# Smartbox.net
KiCad netlist of a schematic drawn in EAGLE
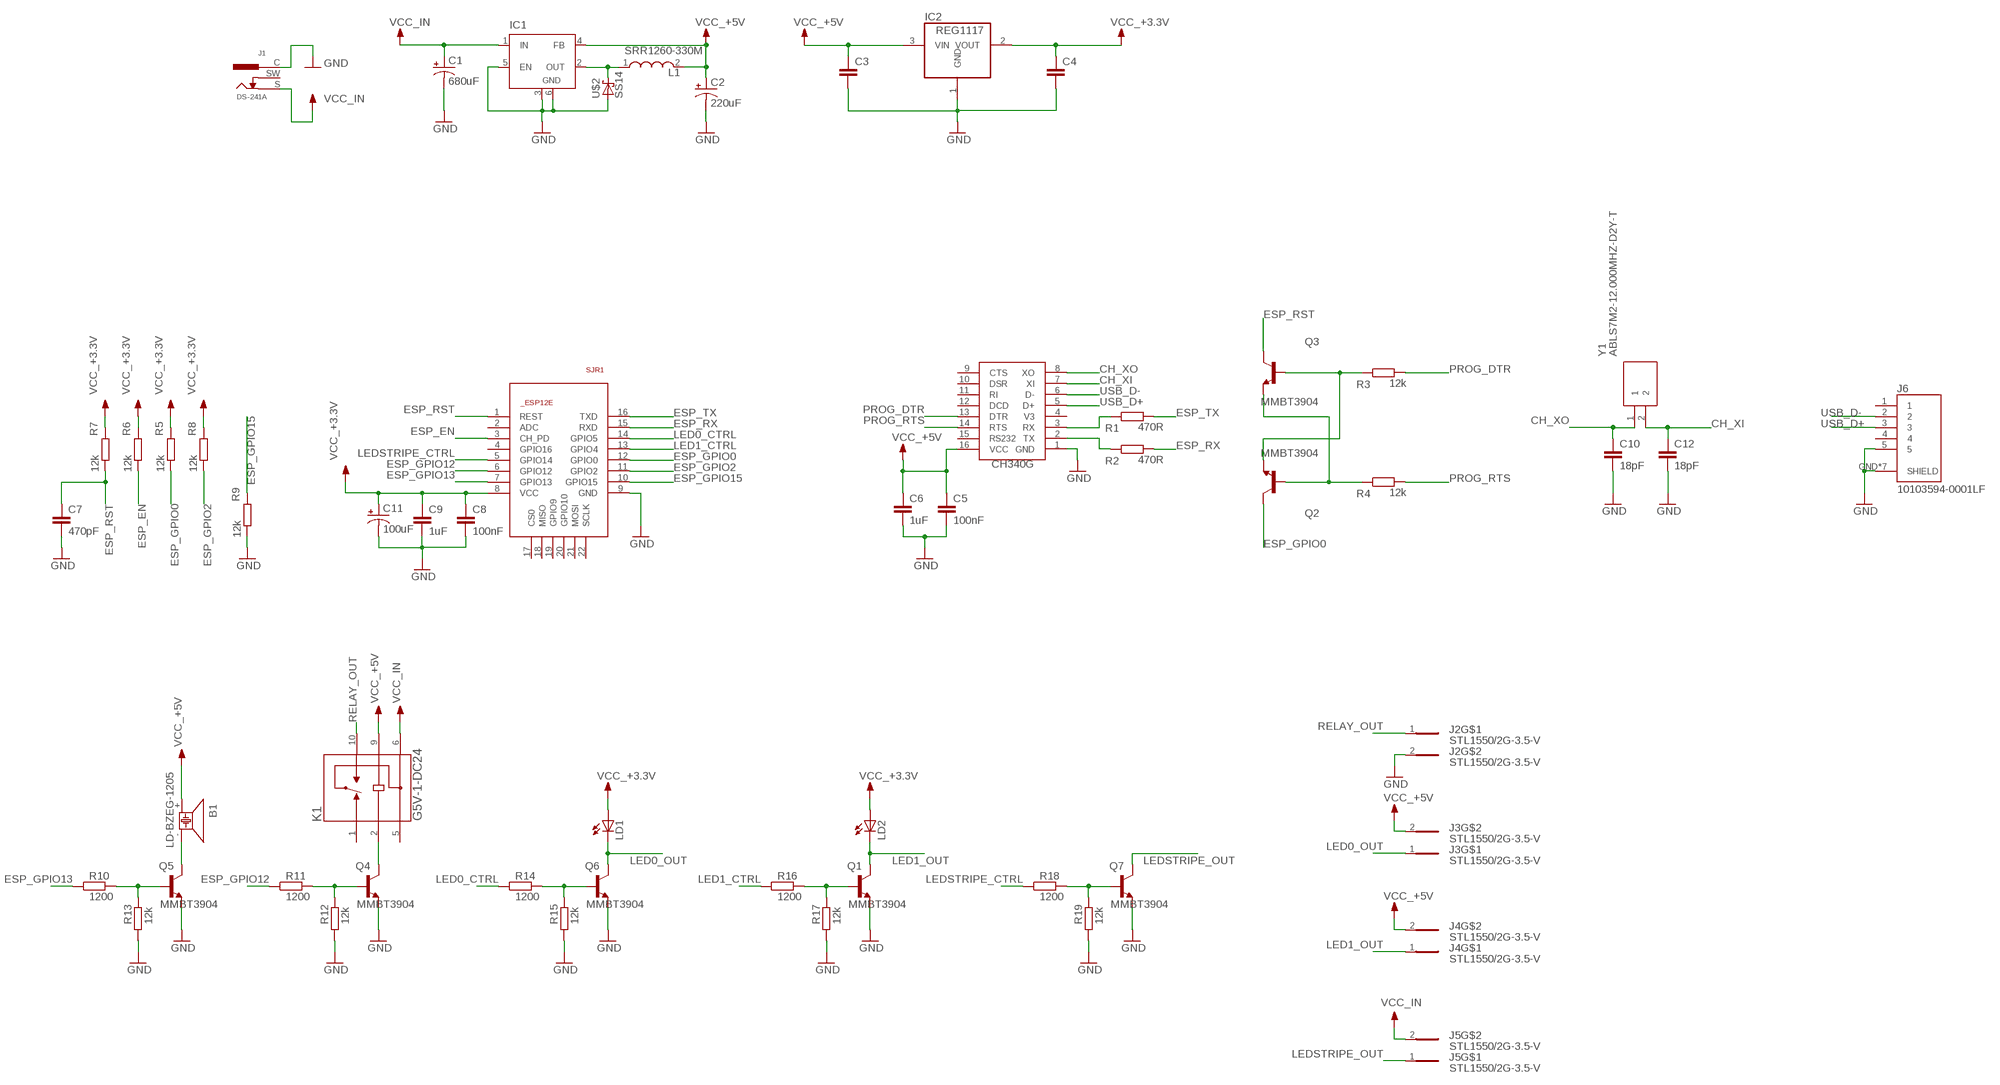
[diagram p0: schematic, sheet 1]

(export (version "E")
  (design (tool "Eeschema 10.0.6"))
  (components
    (comp (ref "B1")
      (value "LD-BZEG-1205")
      (footprint "eagle-import:LD-BZEG-12XX")
      (libsource (lib "eagle-import") (part "LD-BZEG-1205"))
    )
    (comp (ref "C1")
      (value "680uF")
      (footprint "eagle-import:PANASONIC_D")
      (libsource (lib "eagle-import") (part "100UF-POLAR-25V-20%(ELEC)"))
    )
    (comp (ref "C2")
      (value "220uF")
      (footprint "eagle-import:PANASONIC_D")
      (libsource (lib "eagle-import") (part "100UF-POLAR-25V-20%(ELEC)"))
    )
    (comp (ref "C3")
      (value "C-EUC0805")
      (footprint "eagle-import:C0805")
      (libsource (lib "eagle-import") (part "C-EUC0805"))
    )
    (comp (ref "C4")
      (value "C-EUC0805")
      (footprint "eagle-import:C0805")
      (libsource (lib "eagle-import") (part "C-EUC0805"))
    )
    (comp (ref "C5")
      (value "100nF")
      (footprint "eagle-import:C0805")
      (libsource (lib "eagle-import") (part "C-EUC0805"))
    )
    (comp (ref "C6")
      (value "1uF")
      (footprint "eagle-import:C0805")
      (libsource (lib "eagle-import") (part "C-EUC0805"))
    )
    (comp (ref "C7")
      (value "470pF")
      (footprint "eagle-import:C0805")
      (libsource (lib "eagle-import") (part "C-EUC0805"))
    )
    (comp (ref "C8")
      (value "100nF")
      (footprint "eagle-import:C0805")
      (libsource (lib "eagle-import") (part "C-EUC0805"))
    )
    (comp (ref "C9")
      (value "1uF")
      (footprint "eagle-import:C0805")
      (libsource (lib "eagle-import") (part "C-EUC0805"))
    )
    (comp (ref "C10")
      (value "18pF")
      (footprint "eagle-import:C0805")
      (libsource (lib "eagle-import") (part "C-EUC0805"))
    )
    (comp (ref "C11")
      (value "100uF")
      (footprint "eagle-import:PANASONIC_D")
      (libsource (lib "eagle-import") (part "100UF-POLAR-25V-20%(ELEC)"))
    )
    (comp (ref "C12")
      (value "18pF")
      (footprint "eagle-import:C0805")
      (libsource (lib "eagle-import") (part "C-EUC0805"))
    )
    (comp (ref "IC1")
      (value "LM2596S")
      (footprint "eagle-import:TO263-5")
      (libsource (lib "eagle-import") (part "LM2596S"))
    )
    (comp (ref "IC2")
      (value "REG1117")
      (footprint "eagle-import:SOT223")
      (libsource (lib "eagle-import") (part "REG1117"))
    )
    (comp (ref "J1")
      (value "DS-241A")
      (footprint "eagle-import:DS-241")
      (libsource (lib "eagle-import") (part "DS-241A"))
    )
    (comp (ref "J2")
      (value "STL1550/2G-3.5-V")
      (footprint "eagle-import:STL1550_2G-3.5-V-GREEN")
      (libsource (lib "eagle-import") (part "STL1550/2G-3.5-V"))
    )
    (comp (ref "J3")
      (value "STL1550/2G-3.5-V")
      (footprint "eagle-import:STL1550_2G-3.5-V-GREEN")
      (libsource (lib "eagle-import") (part "STL1550/2G-3.5-V"))
    )
    (comp (ref "J4")
      (value "STL1550/2G-3.5-V")
      (footprint "eagle-import:STL1550_2G-3.5-V-GREEN")
      (libsource (lib "eagle-import") (part "STL1550/2G-3.5-V"))
    )
    (comp (ref "J5")
      (value "STL1550/2G-3.5-V")
      (footprint "eagle-import:STL1550_2G-3.5-V-GREEN")
      (libsource (lib "eagle-import") (part "STL1550/2G-3.5-V"))
    )
    (comp (ref "J6")
      (value "10103594-0001LF")
      (footprint "eagle-import:10103594-0001LF")
      (fields
        (field (name "DIGIKEY_PART_NUMBER") "609-4050-2-ND")
        (field (name "MANUFACTURER") "Amphenol ICC (FCI)")
        (field (name "CREATED_BY") "PCBLayout.com")
      )
      (libsource (lib "eagle-import") (part "10103594-0001LF"))
    )
    (comp (ref "K1")
      (value "G5V-1-DC24")
      (footprint "eagle-import:G5V-1-DC24")
      (fields
        (field (name "MANUFACTURER") "Omron Electronics Inc-EMC Div")
        (field (name "CREATED_BY") "  PCBLayout.com")
      )
      (libsource (lib "eagle-import") (part "G5V-1-DC24"))
    )
    (comp (ref "L1")
      (value "SRR1260-330M")
      (footprint "eagle-import:SRR1260-150M")
      (fields (field (name "MOUSER_PART_NUMBER") "652-SRR1260-330M"))
      (libsource (lib "eagle-import") (part "SRR1260-330M"))
    )
    (comp (ref "LD1")
      (value "LEDCHIPLED_0805")
      (footprint "eagle-import:CHIPLED_0805")
      (libsource (lib "eagle-import") (part "LEDCHIPLED_0805"))
    )
    (comp (ref "LD2")
      (value "LEDCHIPLED_0805")
      (footprint "eagle-import:CHIPLED_0805")
      (libsource (lib "eagle-import") (part "LEDCHIPLED_0805"))
    )
    (comp (ref "Q1")
      (value "MMBT3904")
      (footprint "eagle-import:SOT23")
      (fields
        (field (name "DIGIKEY_PART_NUMBER") "MMBT3904FSCT-ND")
        (field (name "MANUFACTURER") "ON Semiconductor")
        (field (name "CREATED_BY") "PCBLayout.com")
      )
      (libsource (lib "eagle-import") (part "MMBT3904"))
    )
    (comp (ref "Q2")
      (value "MMBT3904")
      (footprint "eagle-import:SOT23")
      (fields
        (field (name "DIGIKEY_PART_NUMBER") "MMBT3904FSCT-ND")
        (field (name "MANUFACTURER") "ON Semiconductor")
        (field (name "CREATED_BY") "PCBLayout.com")
      )
      (libsource (lib "eagle-import") (part "MMBT3904"))
    )
    (comp (ref "Q3")
      (value "MMBT3904")
      (footprint "eagle-import:SOT23")
      (fields
        (field (name "DIGIKEY_PART_NUMBER") "MMBT3904FSCT-ND")
        (field (name "MANUFACTURER") "ON Semiconductor")
        (field (name "CREATED_BY") "PCBLayout.com")
      )
      (libsource (lib "eagle-import") (part "MMBT3904"))
    )
    (comp (ref "Q4")
      (value "MMBT3904")
      (footprint "eagle-import:SOT23")
      (fields
        (field (name "DIGIKEY_PART_NUMBER") "MMBT3904FSCT-ND")
        (field (name "MANUFACTURER") "ON Semiconductor")
        (field (name "CREATED_BY") "PCBLayout.com")
      )
      (libsource (lib "eagle-import") (part "MMBT3904"))
    )
    (comp (ref "Q5")
      (value "MMBT3904")
      (footprint "eagle-import:SOT23")
      (fields
        (field (name "DIGIKEY_PART_NUMBER") "MMBT3904FSCT-ND")
        (field (name "MANUFACTURER") "ON Semiconductor")
        (field (name "CREATED_BY") "PCBLayout.com")
      )
      (libsource (lib "eagle-import") (part "MMBT3904"))
    )
    (comp (ref "Q6")
      (value "MMBT3904")
      (footprint "eagle-import:SOT23")
      (fields
        (field (name "DIGIKEY_PART_NUMBER") "MMBT3904FSCT-ND")
        (field (name "MANUFACTURER") "ON Semiconductor")
        (field (name "CREATED_BY") "PCBLayout.com")
      )
      (libsource (lib "eagle-import") (part "MMBT3904"))
    )
    (comp (ref "Q7")
      (value "MMBT3904")
      (footprint "eagle-import:SOT23")
      (fields
        (field (name "DIGIKEY_PART_NUMBER") "MMBT3904FSCT-ND")
        (field (name "MANUFACTURER") "ON Semiconductor")
        (field (name "CREATED_BY") "PCBLayout.com")
      )
      (libsource (lib "eagle-import") (part "MMBT3904"))
    )
    (comp (ref "R1")
      (value "470R")
      (footprint "eagle-import:R0805")
      (libsource (lib "eagle-import") (part "R-EU_R0805"))
    )
    (comp (ref "R2")
      (value "470R")
      (footprint "eagle-import:R0805")
      (libsource (lib "eagle-import") (part "R-EU_R0805"))
    )
    (comp (ref "R3")
      (value "12k")
      (footprint "eagle-import:R0805")
      (libsource (lib "eagle-import") (part "R-EU_R0805"))
    )
    (comp (ref "R4")
      (value "12k")
      (footprint "eagle-import:R0805")
      (libsource (lib "eagle-import") (part "R-EU_R0805"))
    )
    (comp (ref "R5")
      (value "12k")
      (footprint "eagle-import:R0805")
      (libsource (lib "eagle-import") (part "R-EU_R0805"))
    )
    (comp (ref "R6")
      (value "12k")
      (footprint "eagle-import:R0805")
      (libsource (lib "eagle-import") (part "R-EU_R0805"))
    )
    (comp (ref "R7")
      (value "12k")
      (footprint "eagle-import:R0805")
      (libsource (lib "eagle-import") (part "R-EU_R0805"))
    )
    (comp (ref "R8")
      (value "12k")
      (footprint "eagle-import:R0805")
      (libsource (lib "eagle-import") (part "R-EU_R0805"))
    )
    (comp (ref "R9")
      (value "12k")
      (footprint "eagle-import:R0805")
      (libsource (lib "eagle-import") (part "R-EU_R0805"))
    )
    (comp (ref "R10")
      (value "1200")
      (footprint "eagle-import:R0805")
      (libsource (lib "eagle-import") (part "R-EU_R0805"))
    )
    (comp (ref "R11")
      (value "1200")
      (footprint "eagle-import:R0805")
      (libsource (lib "eagle-import") (part "R-EU_R0805"))
    )
    (comp (ref "R12")
      (value "12k")
      (footprint "eagle-import:R0805")
      (libsource (lib "eagle-import") (part "R-EU_R0805"))
    )
    (comp (ref "R13")
      (value "12k")
      (footprint "eagle-import:R0805")
      (libsource (lib "eagle-import") (part "R-EU_R0805"))
    )
    (comp (ref "R14")
      (value "1200")
      (footprint "eagle-import:R0805")
      (libsource (lib "eagle-import") (part "R-EU_R0805"))
    )
    (comp (ref "R15")
      (value "12k")
      (footprint "eagle-import:R0805")
      (libsource (lib "eagle-import") (part "R-EU_R0805"))
    )
    (comp (ref "R16")
      (value "1200")
      (footprint "eagle-import:R0805")
      (libsource (lib "eagle-import") (part "R-EU_R0805"))
    )
    (comp (ref "R17")
      (value "12k")
      (footprint "eagle-import:R0805")
      (libsource (lib "eagle-import") (part "R-EU_R0805"))
    )
    (comp (ref "R18")
      (value "1200")
      (footprint "eagle-import:R0805")
      (libsource (lib "eagle-import") (part "R-EU_R0805"))
    )
    (comp (ref "R19")
      (value "12k")
      (footprint "eagle-import:R0805")
      (libsource (lib "eagle-import") (part "R-EU_R0805"))
    )
    (comp (ref "SJR1")
      (value "ESP8266-12EESP12E")
      (footprint "eagle-import:ESP8266-ESP12E")
      (libsource (lib "eagle-import") (part "ESP8266-12EESP12E"))
    )
    (comp (ref "U$2")
      (value "SS14")
      (footprint "eagle-import:DO-214AC")
      (fields (field (name "MF") "ON Semiconductor"))
      (libsource (lib "eagle-import") (part "SS14"))
    )
    (comp (ref "U$3")
      (value "CH340G")
      (footprint "eagle-import:SOIC16")
      (libsource (lib "eagle-import") (part "CH340G"))
    )
    (comp (ref "Y1")
      (value "ABLS7M2-12.000MHZ-D2Y-T")
      (footprint "eagle-import:ABLS7M216000MHZD2YT")
      (fields
        (field (name "MANUFACTURER_PART_NUMBER") "ABLS7M2-16.000MHZ-D2Y-T")
        (field (name "MOUSER_PART_NUMBER") "815-ABLS7M216MHZD2YT")
      )
      (libsource (lib "eagle-import") (part "ABLS7M2-16.000MHZ-D2Y-T"))
    )
  )
  (nets
    (net (code "1") (name "/CH_XI") (class "Default")
      (node (ref "C12") (pin "1") (pinfunction "1_1") (pintype "passive"))
      (node (ref "U$3") (pin "7") (pinfunction "XI_7") (pintype "bidirectional"))
      (node (ref "Y1") (pin "2") (pinfunction "2_2") (pintype "bidirectional"))
    )
    (net (code "2") (name "/CH_XO") (class "Default")
      (node (ref "C10") (pin "1") (pinfunction "1_1") (pintype "passive"))
      (node (ref "U$3") (pin "8") (pinfunction "XO_8") (pintype "bidirectional"))
      (node (ref "Y1") (pin "1") (pinfunction "1_1") (pintype "bidirectional"))
    )
    (net (code "3") (name "/ESP_EN") (class "Default")
      (node (ref "R6") (pin "2") (pinfunction "2_2") (pintype "passive"))
      (node (ref "SJR1") (pin "3") (pinfunction "CH_PD_3") (pintype "bidirectional"))
    )
    (net (code "4") (name "/ESP_GPIO0") (class "Default")
      (node (ref "Q2") (pin "3") (pinfunction "C_3") (pintype "passive"))
      (node (ref "R5") (pin "2") (pinfunction "2_2") (pintype "passive"))
      (node (ref "SJR1") (pin "12") (pinfunction "GPIO0_12") (pintype "bidirectional"))
    )
    (net (code "5") (name "/ESP_GPIO2") (class "Default")
      (node (ref "R8") (pin "2") (pinfunction "2_2") (pintype "passive"))
      (node (ref "SJR1") (pin "11") (pinfunction "GPIO2_11") (pintype "bidirectional"))
    )
    (net (code "6") (name "/ESP_GPIO12") (class "Default")
      (node (ref "R11") (pin "1") (pinfunction "1_1") (pintype "passive"))
      (node (ref "SJR1") (pin "6") (pinfunction "GPIO12_6") (pintype "bidirectional"))
    )
    (net (code "7") (name "/ESP_GPIO13") (class "Default")
      (node (ref "R10") (pin "1") (pinfunction "1_1") (pintype "passive"))
      (node (ref "SJR1") (pin "7") (pinfunction "GPIO13_7") (pintype "bidirectional"))
    )
    (net (code "8") (name "/ESP_GPIO15") (class "Default")
      (node (ref "R9") (pin "1") (pinfunction "1_1") (pintype "passive"))
      (node (ref "SJR1") (pin "10") (pinfunction "GPIO15_10") (pintype "bidirectional"))
    )
    (net (code "9") (name "/ESP_RST") (class "Default")
      (node (ref "C7") (pin "1") (pinfunction "1_1") (pintype "passive"))
      (node (ref "Q3") (pin "3") (pinfunction "C_3") (pintype "passive"))
      (node (ref "R7") (pin "2") (pinfunction "2_2") (pintype "passive"))
      (node (ref "SJR1") (pin "1") (pinfunction "REST_1") (pintype "bidirectional"))
    )
    (net (code "10") (name "/ESP_RX") (class "Default")
      (node (ref "R2") (pin "2") (pinfunction "2_2") (pintype "passive"))
      (node (ref "SJR1") (pin "15") (pinfunction "RXD_15") (pintype "bidirectional"))
    )
    (net (code "11") (name "/ESP_TX") (class "Default")
      (node (ref "R1") (pin "2") (pinfunction "2_2") (pintype "passive"))
      (node (ref "SJR1") (pin "16") (pinfunction "TXD_16") (pintype "bidirectional"))
    )
    (net (code "12") (name "/LED0_CTRL") (class "Default")
      (node (ref "R14") (pin "1") (pinfunction "1_1") (pintype "passive"))
      (node (ref "SJR1") (pin "14") (pinfunction "GPIO5_14") (pintype "bidirectional"))
    )
    (net (code "13") (name "/LED0_OUT") (class "Default")
      (node (ref "J3") (pin "1") (pinfunction "1_1") (pintype "passive"))
      (node (ref "LD1") (pin "C") (pinfunction "C_C") (pintype "passive"))
      (node (ref "Q6") (pin "3") (pinfunction "C_3") (pintype "passive"))
    )
    (net (code "14") (name "/LED1_CTRL") (class "Default")
      (node (ref "R16") (pin "1") (pinfunction "1_1") (pintype "passive"))
      (node (ref "SJR1") (pin "13") (pinfunction "GPIO4_13") (pintype "bidirectional"))
    )
    (net (code "15") (name "/LED1_OUT") (class "Default")
      (node (ref "J4") (pin "1") (pinfunction "1_1") (pintype "passive"))
      (node (ref "LD2") (pin "C") (pinfunction "C_C") (pintype "passive"))
      (node (ref "Q1") (pin "3") (pinfunction "C_3") (pintype "passive"))
    )
    (net (code "16") (name "/LEDSTRIPE_CTRL") (class "Default")
      (node (ref "R18") (pin "1") (pinfunction "1_1") (pintype "passive"))
      (node (ref "SJR1") (pin "5") (pinfunction "GPIO14_5") (pintype "bidirectional"))
    )
    (net (code "17") (name "/LEDSTRIPE_OUT") (class "Default")
      (node (ref "J5") (pin "1") (pinfunction "1_1") (pintype "passive"))
      (node (ref "Q7") (pin "3") (pinfunction "C_3") (pintype "passive"))
    )
    (net (code "18") (name "/PROG_DTR") (class "Default")
      (node (ref "R3") (pin "2") (pinfunction "2_2") (pintype "passive"))
      (node (ref "U$3") (pin "13") (pinfunction "DTR_13") (pintype "bidirectional"))
    )
    (net (code "19") (name "/PROG_RTS") (class "Default")
      (node (ref "R4") (pin "2") (pinfunction "2_2") (pintype "passive"))
      (node (ref "U$3") (pin "14") (pinfunction "RTS_14") (pintype "bidirectional"))
    )
    (net (code "20") (name "/RELAY_OUT") (class "Default")
      (node (ref "J2") (pin "1") (pinfunction "1_1") (pintype "passive"))
      (node (ref "K1") (pin "10") (pinfunction "10_10") (pintype "passive"))
    )
    (net (code "21") (name "/USB_D+") (class "Default")
      (node (ref "J6") (pin "3") (pinfunction "3_3") (pintype "passive"))
      (node (ref "U$3") (pin "5") (pinfunction "D+_5") (pintype "bidirectional"))
    )
    (net (code "22") (name "/USB_D-") (class "Default")
      (node (ref "J6") (pin "2") (pinfunction "2_2") (pintype "passive"))
      (node (ref "U$3") (pin "6") (pinfunction "D-_6") (pintype "bidirectional"))
    )
    (net (code "23") (name "GND") (class "Default")
      (node (ref "C1") (pin "-") (pinfunction "-_-") (pintype "passive"))
      (node (ref "C10") (pin "2") (pinfunction "2_2") (pintype "passive"))
      (node (ref "C11") (pin "-") (pinfunction "-_-") (pintype "passive"))
      (node (ref "C12") (pin "2") (pinfunction "2_2") (pintype "passive"))
      (node (ref "C2") (pin "-") (pinfunction "-_-") (pintype "passive"))
      (node (ref "C3") (pin "2") (pinfunction "2_2") (pintype "passive"))
      (node (ref "C4") (pin "2") (pinfunction "2_2") (pintype "passive"))
      (node (ref "C5") (pin "2") (pinfunction "2_2") (pintype "passive"))
      (node (ref "C6") (pin "2") (pinfunction "2_2") (pintype "passive"))
      (node (ref "C7") (pin "2") (pinfunction "2_2") (pintype "passive"))
      (node (ref "C8") (pin "2") (pinfunction "2_2") (pintype "passive"))
      (node (ref "C9") (pin "2") (pinfunction "2_2") (pintype "passive"))
      (node (ref "IC1") (pin "3") (pinfunction "GND_3") (pintype "power_in"))
      (node (ref "IC1") (pin "5") (pinfunction "EN_5") (pintype "input"))
      (node (ref "IC1") (pin "6") (pinfunction "GND_6") (pintype "power_in"))
      (node (ref "IC2") (pin "1") (pinfunction "GND_1") (pintype "power_in"))
      (node (ref "J1") (pin "C") (pinfunction "C_C") (pintype "passive"))
      (node (ref "J2") (pin "2") (pinfunction "1_2") (pintype "passive"))
      (node (ref "J6") (pin "5") (pinfunction "5_5") (pintype "passive"))
      (node (ref "J6") (pin "GND") (pinfunction "SHIELD_GND") (pintype "passive"))
      (node (ref "J6") (pin "GND$1") (pinfunction "SHIELD_GND$1") (pintype "passive"))
      (node (ref "J6") (pin "GND$2") (pinfunction "SHIELD_GND$2") (pintype "passive"))
      (node (ref "J6") (pin "S1") (pinfunction "SHIELD_S1") (pintype "passive"))
      (node (ref "J6") (pin "S2") (pinfunction "SHIELD_S2") (pintype "passive"))
      (node (ref "J6") (pin "S3") (pinfunction "SHIELD_S3") (pintype "passive"))
      (node (ref "J6") (pin "S4") (pinfunction "SHIELD_S4") (pintype "passive"))
      (node (ref "Q1") (pin "2") (pinfunction "E_2") (pintype "passive"))
      (node (ref "Q4") (pin "2") (pinfunction "E_2") (pintype "passive"))
      (node (ref "Q5") (pin "2") (pinfunction "E_2") (pintype "passive"))
      (node (ref "Q6") (pin "2") (pinfunction "E_2") (pintype "passive"))
      (node (ref "Q7") (pin "2") (pinfunction "E_2") (pintype "passive"))
      (node (ref "R12") (pin "1") (pinfunction "1_1") (pintype "passive"))
      (node (ref "R13") (pin "1") (pinfunction "1_1") (pintype "passive"))
      (node (ref "R15") (pin "1") (pinfunction "1_1") (pintype "passive"))
      (node (ref "R17") (pin "1") (pinfunction "1_1") (pintype "passive"))
      (node (ref "R19") (pin "1") (pinfunction "1_1") (pintype "passive"))
      (node (ref "R9") (pin "2") (pinfunction "2_2") (pintype "passive"))
      (node (ref "SJR1") (pin "9") (pinfunction "GND_9") (pintype "bidirectional"))
      (node (ref "U$2") (pin "A") (pinfunction "A_A") (pintype "passive"))
      (node (ref "U$3") (pin "1") (pinfunction "GND_1") (pintype "bidirectional"))
    )
    (net (code "24") (name "Net-(IC1-OUT)") (class "Default")
      (node (ref "IC1") (pin "2") (pinfunction "OUT_2") (pintype "output"))
      (node (ref "L1") (pin "1") (pinfunction "1_1") (pintype "bidirectional"))
      (node (ref "U$2") (pin "C") (pinfunction "C_C") (pintype "passive"))
    )
    (net (code "25") (name "Net-(Q1-B)") (class "Default")
      (node (ref "Q1") (pin "1") (pinfunction "B_1") (pintype "passive"))
      (node (ref "R16") (pin "2") (pinfunction "2_2") (pintype "passive"))
      (node (ref "R17") (pin "2") (pinfunction "2_2") (pintype "passive"))
    )
    (net (code "26") (name "Net-(Q2-B)") (class "Default")
      (node (ref "Q2") (pin "1") (pinfunction "B_1") (pintype "passive"))
      (node (ref "Q3") (pin "2") (pinfunction "E_2") (pintype "passive"))
      (node (ref "R4") (pin "1") (pinfunction "1_1") (pintype "passive"))
    )
    (net (code "27") (name "Net-(Q2-E)") (class "Default")
      (node (ref "Q2") (pin "2") (pinfunction "E_2") (pintype "passive"))
      (node (ref "Q3") (pin "1") (pinfunction "B_1") (pintype "passive"))
      (node (ref "R3") (pin "1") (pinfunction "1_1") (pintype "passive"))
    )
    (net (code "28") (name "Net-(Q4-B)") (class "Default")
      (node (ref "Q4") (pin "1") (pinfunction "B_1") (pintype "passive"))
      (node (ref "R11") (pin "2") (pinfunction "2_2") (pintype "passive"))
      (node (ref "R12") (pin "2") (pinfunction "2_2") (pintype "passive"))
    )
    (net (code "29") (name "Net-(Q4-C)") (class "Default")
      (node (ref "K1") (pin "2") (pinfunction "2_2") (pintype "passive"))
      (node (ref "Q4") (pin "3") (pinfunction "C_3") (pintype "passive"))
    )
    (net (code "30") (name "Net-(Q5-B)") (class "Default")
      (node (ref "Q5") (pin "1") (pinfunction "B_1") (pintype "passive"))
      (node (ref "R10") (pin "2") (pinfunction "2_2") (pintype "passive"))
      (node (ref "R13") (pin "2") (pinfunction "2_2") (pintype "passive"))
    )
    (net (code "31") (name "Net-(Q5-C)") (class "Default")
      (node (ref "B1") (pin "-") (pinfunction "-_-") (pintype "passive"))
      (node (ref "Q5") (pin "3") (pinfunction "C_3") (pintype "passive"))
    )
    (net (code "32") (name "Net-(Q6-B)") (class "Default")
      (node (ref "Q6") (pin "1") (pinfunction "B_1") (pintype "passive"))
      (node (ref "R14") (pin "2") (pinfunction "2_2") (pintype "passive"))
      (node (ref "R15") (pin "2") (pinfunction "2_2") (pintype "passive"))
    )
    (net (code "33") (name "Net-(Q7-B)") (class "Default")
      (node (ref "Q7") (pin "1") (pinfunction "B_1") (pintype "passive"))
      (node (ref "R18") (pin "2") (pinfunction "2_2") (pintype "passive"))
      (node (ref "R19") (pin "2") (pinfunction "2_2") (pintype "passive"))
    )
    (net (code "34") (name "Net-(U$3-RX)") (class "Default")
      (node (ref "R1") (pin "1") (pinfunction "1_1") (pintype "passive"))
      (node (ref "U$3") (pin "3") (pinfunction "RX_3") (pintype "bidirectional"))
    )
    (net (code "35") (name "Net-(U$3-TX)") (class "Default")
      (node (ref "R2") (pin "1") (pinfunction "1_1") (pintype "passive"))
      (node (ref "U$3") (pin "2") (pinfunction "TX_2") (pintype "bidirectional"))
    )
    (net (code "36") (name "VCC_+3.3V") (class "Default")
      (node (ref "C11") (pin "+") (pinfunction "+_+") (pintype "passive"))
      (node (ref "C4") (pin "1") (pinfunction "1_1") (pintype "passive"))
      (node (ref "C8") (pin "1") (pinfunction "1_1") (pintype "passive"))
      (node (ref "C9") (pin "1") (pinfunction "1_1") (pintype "passive"))
      (node (ref "IC2") (pin "2") (pinfunction "VOUT_2") (pintype "output"))
      (node (ref "LD1") (pin "A") (pinfunction "A_A") (pintype "passive"))
      (node (ref "LD2") (pin "A") (pinfunction "A_A") (pintype "passive"))
      (node (ref "R5") (pin "1") (pinfunction "1_1") (pintype "passive"))
      (node (ref "R6") (pin "1") (pinfunction "1_1") (pintype "passive"))
      (node (ref "R7") (pin "1") (pinfunction "1_1") (pintype "passive"))
      (node (ref "R8") (pin "1") (pinfunction "1_1") (pintype "passive"))
      (node (ref "SJR1") (pin "8") (pinfunction "VCC_8") (pintype "bidirectional"))
    )
    (net (code "37") (name "VCC_+5V") (class "Default")
      (node (ref "B1") (pin "+") (pinfunction "+_+") (pintype "passive"))
      (node (ref "C2") (pin "+") (pinfunction "+_+") (pintype "passive"))
      (node (ref "C3") (pin "1") (pinfunction "1_1") (pintype "passive"))
      (node (ref "C5") (pin "1") (pinfunction "1_1") (pintype "passive"))
      (node (ref "C6") (pin "1") (pinfunction "1_1") (pintype "passive"))
      (node (ref "IC1") (pin "4") (pinfunction "FB_4") (pintype "input"))
      (node (ref "IC2") (pin "3") (pinfunction "VIN_3") (pintype "input"))
      (node (ref "J3") (pin "2") (pinfunction "1_2") (pintype "passive"))
      (node (ref "J4") (pin "2") (pinfunction "1_2") (pintype "passive"))
      (node (ref "K1") (pin "9") (pinfunction "9_9") (pintype "passive"))
      (node (ref "L1") (pin "2") (pinfunction "2_2") (pintype "bidirectional"))
      (node (ref "U$3") (pin "16") (pinfunction "VCC_16") (pintype "bidirectional"))
    )
    (net (code "38") (name "VCC_IN") (class "Default")
      (node (ref "C1") (pin "+") (pinfunction "+_+") (pintype "passive"))
      (node (ref "IC1") (pin "1") (pinfunction "IN_1") (pintype "input"))
      (node (ref "J1") (pin "S") (pinfunction "S_S") (pintype "passive"))
      (node (ref "J5") (pin "2") (pinfunction "1_2") (pintype "passive"))
      (node (ref "K1") (pin "6") (pinfunction "6_6") (pintype "passive"))
    )
    (net (code "39") (name "unconnected-(J1-PadSW)") (class "Default")
      (node (ref "J1") (pin "SW") (pinfunction "SW_SW") (pintype "passive"))
    )
    (net (code "40") (name "unconnected-(J6-Pad1)") (class "Default")
      (node (ref "J6") (pin "1") (pinfunction "1_1") (pintype "passive"))
    )
    (net (code "41") (name "unconnected-(J6-Pad4)") (class "Default")
      (node (ref "J6") (pin "4") (pinfunction "4_4") (pintype "passive"))
    )
    (net (code "42") (name "unconnected-(K1-Pad1)") (class "Default")
      (node (ref "K1") (pin "1") (pinfunction "1_1") (pintype "passive"))
    )
    (net (code "43") (name "unconnected-(K1-Pad5)") (class "Default")
      (node (ref "K1") (pin "5") (pinfunction "5_5") (pintype "passive"))
    )
    (net (code "44") (name "unconnected-(SJR1-ADC-Pad2)") (class "Default")
      (node (ref "SJR1") (pin "2") (pinfunction "ADC_2") (pintype "bidirectional"))
    )
    (net (code "45") (name "unconnected-(SJR1-CS0-Pad17)") (class "Default")
      (node (ref "SJR1") (pin "17") (pinfunction "CS0_17") (pintype "bidirectional"))
    )
    (net (code "46") (name "unconnected-(SJR1-GPIO9-Pad19)") (class "Default")
      (node (ref "SJR1") (pin "19") (pinfunction "GPIO9_19") (pintype "bidirectional"))
    )
    (net (code "47") (name "unconnected-(SJR1-GPIO10-Pad20)") (class "Default")
      (node (ref "SJR1") (pin "20") (pinfunction "GPIO10_20") (pintype "bidirectional"))
    )
    (net (code "48") (name "unconnected-(SJR1-GPIO16-Pad4)") (class "Default")
      (node (ref "SJR1") (pin "4") (pinfunction "GPIO16_4") (pintype "bidirectional"))
    )
    (net (code "49") (name "unconnected-(SJR1-MISO-Pad18)") (class "Default")
      (node (ref "SJR1") (pin "18") (pinfunction "MISO_18") (pintype "bidirectional"))
    )
    (net (code "50") (name "unconnected-(SJR1-MOSI-Pad21)") (class "Default")
      (node (ref "SJR1") (pin "21") (pinfunction "MOSI_21") (pintype "bidirectional"))
    )
    (net (code "51") (name "unconnected-(SJR1-SCLK-Pad22)") (class "Default")
      (node (ref "SJR1") (pin "22") (pinfunction "SCLK_22") (pintype "bidirectional"))
    )
    (net (code "52") (name "unconnected-(U$3-CTS-Pad9)") (class "Default")
      (node (ref "U$3") (pin "9") (pinfunction "CTS_9") (pintype "bidirectional"))
    )
    (net (code "53") (name "unconnected-(U$3-DCD-Pad12)") (class "Default")
      (node (ref "U$3") (pin "12") (pinfunction "DCD_12") (pintype "bidirectional"))
    )
    (net (code "54") (name "unconnected-(U$3-DSR-Pad10)") (class "Default")
      (node (ref "U$3") (pin "10") (pinfunction "DSR_10") (pintype "bidirectional"))
    )
    (net (code "55") (name "unconnected-(U$3-RI-Pad11)") (class "Default")
      (node (ref "U$3") (pin "11") (pinfunction "RI_11") (pintype "bidirectional"))
    )
    (net (code "56") (name "unconnected-(U$3-RS232-Pad15)") (class "Default")
      (node (ref "U$3") (pin "15") (pinfunction "RS232_15") (pintype "bidirectional"))
    )
    (net (code "57") (name "unconnected-(U$3-V3-Pad4)") (class "Default")
      (node (ref "U$3") (pin "4") (pinfunction "V3_4") (pintype "bidirectional"))
    )
  )
)
